# Off-Board_Connections.net
KiCad netlist of a schematic drawn in Altium Designer
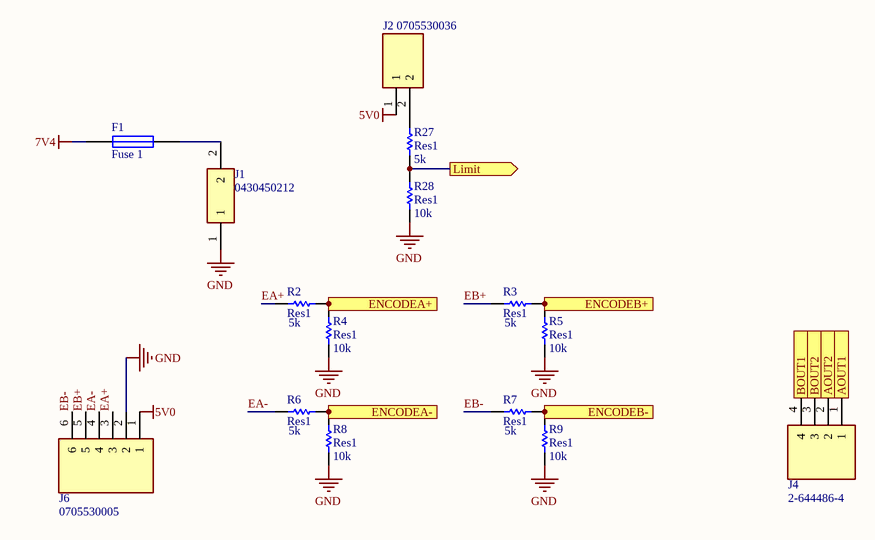
[diagram p0: Off-Board Connections.SchDoc]

(export (version "E")
  (design (tool "Eeschema 10.0.6"))
  (components
    (comp (ref "F1")
      (value "Fuse 1")
      (footprint "C1206")
      (description "Fuse")
      (fields (field (name "PUBLISHER") "Altium Limited"))
      (libsource (lib "Miscellaneous Devices") (part "Fuse 1"))
    )
    (comp (ref "J1")
      (value "0430450212")
      (footprint "0430450212")
      (description "Connector")
      (libsource (lib "SamacSys") (part "0430450212"))
    )
    (comp (ref "J2")
      (value "0705530036")
      (footprint "SamacSys:SHDRRA2W64P0X254_1X2_737X1359X699P")
      (description "Connector")
      (libsource (lib "*") (part "0705530036"))
    )
    (comp (ref "J4")
      (value "2-644486-4")
      (footprint "SamacSys:26444864")
      (description "Connector")
      (fields (field (name "MOUSER PART NUMBER") "571-2-644486-4"))
      (libsource (lib "*") (part "2-644486-4"))
    )
    (comp (ref "J6")
      (value "0705530005")
      (footprint "SamacSys:SHDRRA6W64P0X254_1X6_1779X1359X699P")
      (description "Connector")
      (libsource (lib "*") (part "0705530005"))
    )
    (comp (ref "R2")
      (value "Res1")
      (footprint "0402-A")
      (description "Resistor")
      (fields (field (name "ALTIUM_VALUE") "5k") (field (name "PUBLISHER") "Altium Limited"))
      (libsource (lib "Miscellaneous Devices") (part "Res1"))
    )
    (comp (ref "R3")
      (value "Res1")
      (footprint "0402-A")
      (description "Resistor")
      (fields (field (name "ALTIUM_VALUE") "5k") (field (name "PUBLISHER") "Altium Limited"))
      (libsource (lib "Miscellaneous Devices") (part "Res1"))
    )
    (comp (ref "R4")
      (value "Res1")
      (footprint "0402-A")
      (description "Resistor")
      (fields (field (name "ALTIUM_VALUE") "10k") (field (name "PUBLISHER") "Altium Limited"))
      (libsource (lib "Miscellaneous Devices") (part "Res1"))
    )
    (comp (ref "R5")
      (value "Res1")
      (footprint "0402-A")
      (description "Resistor")
      (fields (field (name "ALTIUM_VALUE") "10k") (field (name "PUBLISHER") "Altium Limited"))
      (libsource (lib "Miscellaneous Devices") (part "Res1"))
    )
    (comp (ref "R6")
      (value "Res1")
      (footprint "0402-A")
      (description "Resistor")
      (fields (field (name "ALTIUM_VALUE") "5k") (field (name "PUBLISHER") "Altium Limited"))
      (libsource (lib "Miscellaneous Devices") (part "Res1"))
    )
    (comp (ref "R7")
      (value "Res1")
      (footprint "0402-A")
      (description "Resistor")
      (fields (field (name "ALTIUM_VALUE") "5k") (field (name "PUBLISHER") "Altium Limited"))
      (libsource (lib "Miscellaneous Devices") (part "Res1"))
    )
    (comp (ref "R8")
      (value "Res1")
      (footprint "0402-A")
      (description "Resistor")
      (fields (field (name "ALTIUM_VALUE") "10k") (field (name "PUBLISHER") "Altium Limited"))
      (libsource (lib "Miscellaneous Devices") (part "Res1"))
    )
    (comp (ref "R9")
      (value "Res1")
      (footprint "0402-A")
      (description "Resistor")
      (fields (field (name "ALTIUM_VALUE") "10k") (field (name "PUBLISHER") "Altium Limited"))
      (libsource (lib "Miscellaneous Devices") (part "Res1"))
    )
    (comp (ref "R27")
      (value "Res1")
      (footprint "0402-A")
      (description "Resistor")
      (fields (field (name "ALTIUM_VALUE") "5k") (field (name "PUBLISHER") "Altium Limited"))
      (libsource (lib "Miscellaneous Devices") (part "Res1"))
    )
    (comp (ref "R28")
      (value "Res1")
      (footprint "0402-A")
      (description "Resistor")
      (fields (field (name "ALTIUM_VALUE") "10k") (field (name "PUBLISHER") "Altium Limited"))
      (libsource (lib "Miscellaneous Devices") (part "Res1"))
    )
  )
  (nets
    (net (code "1") (name "/AOUT1") (class "Default")
      (node (ref "J4") (pin "1") (pinfunction "1_1") (pintype "passive"))
    )
    (net (code "2") (name "/AOUT2") (class "Default")
      (node (ref "J4") (pin "2") (pinfunction "2_2") (pintype "passive"))
    )
    (net (code "3") (name "/BOUT1") (class "Default")
      (node (ref "J4") (pin "4") (pinfunction "4_4") (pintype "passive"))
    )
    (net (code "4") (name "/BOUT2") (class "Default")
      (node (ref "J4") (pin "3") (pinfunction "3_3") (pintype "passive"))
    )
    (net (code "5") (name "/EA+") (class "Default")
      (node (ref "J6") (pin "3") (pinfunction "3_3") (pintype "passive"))
      (node (ref "R2") (pin "2") (pinfunction "2_2") (pintype "passive"))
    )
    (net (code "6") (name "/EA-") (class "Default")
      (node (ref "J6") (pin "4") (pinfunction "4_4") (pintype "passive"))
      (node (ref "R6") (pin "2") (pinfunction "2_2") (pintype "passive"))
    )
    (net (code "7") (name "/EB+") (class "Default")
      (node (ref "J6") (pin "5") (pinfunction "5_5") (pintype "passive"))
      (node (ref "R3") (pin "2") (pinfunction "2_2") (pintype "passive"))
    )
    (net (code "8") (name "/EB-") (class "Default")
      (node (ref "J6") (pin "6") (pinfunction "6_6") (pintype "passive"))
      (node (ref "R7") (pin "2") (pinfunction "2_2") (pintype "passive"))
    )
    (net (code "9") (name "/ENCODEA+") (class "Default")
      (node (ref "R2") (pin "1") (pinfunction "1_1") (pintype "passive"))
      (node (ref "R4") (pin "1") (pinfunction "1_1") (pintype "passive"))
    )
    (net (code "10") (name "/ENCODEA-") (class "Default")
      (node (ref "R6") (pin "1") (pinfunction "1_1") (pintype "passive"))
      (node (ref "R8") (pin "1") (pinfunction "1_1") (pintype "passive"))
    )
    (net (code "11") (name "/ENCODEB+") (class "Default")
      (node (ref "R3") (pin "1") (pinfunction "1_1") (pintype "passive"))
      (node (ref "R5") (pin "1") (pinfunction "1_1") (pintype "passive"))
    )
    (net (code "12") (name "/ENCODEB-") (class "Default")
      (node (ref "R7") (pin "1") (pinfunction "1_1") (pintype "passive"))
      (node (ref "R9") (pin "1") (pinfunction "1_1") (pintype "passive"))
    )
    (net (code "13") (name "/Limit") (class "Default")
      (node (ref "R27") (pin "2") (pinfunction "2_2") (pintype "passive"))
      (node (ref "R28") (pin "1") (pinfunction "1_1") (pintype "passive"))
    )
    (net (code "14") (name "5V0") (class "Default")
      (node (ref "J2") (pin "1") (pinfunction "1_1") (pintype "passive"))
      (node (ref "J6") (pin "1") (pinfunction "1_1") (pintype "passive"))
    )
    (net (code "15") (name "7V4") (class "Default")
      (node (ref "F1") (pin "1") (pinfunction "1_1") (pintype "passive"))
    )
    (net (code "16") (name "GND") (class "Default")
      (node (ref "J1") (pin "1") (pinfunction "1_1") (pintype "passive"))
      (node (ref "J6") (pin "2") (pinfunction "2_2") (pintype "passive"))
      (node (ref "R28") (pin "2") (pinfunction "2_2") (pintype "passive"))
      (node (ref "R4") (pin "2") (pinfunction "2_2") (pintype "passive"))
      (node (ref "R5") (pin "2") (pinfunction "2_2") (pintype "passive"))
      (node (ref "R8") (pin "2") (pinfunction "2_2") (pintype "passive"))
      (node (ref "R9") (pin "2") (pinfunction "2_2") (pintype "passive"))
    )
    (net (code "17") (name "Net-(F1-Pad2)") (class "Default")
      (node (ref "F1") (pin "2") (pinfunction "2_2") (pintype "passive"))
      (node (ref "J1") (pin "2") (pinfunction "2_2") (pintype "passive"))
    )
    (net (code "18") (name "Net-(J2-Pad2)") (class "Default")
      (node (ref "J2") (pin "2") (pinfunction "2_2") (pintype "passive"))
      (node (ref "R27") (pin "1") (pinfunction "1_1") (pintype "passive"))
    )
  )
)
